# Level_Shifter.net
KiCad netlist of a schematic drawn in EAGLE
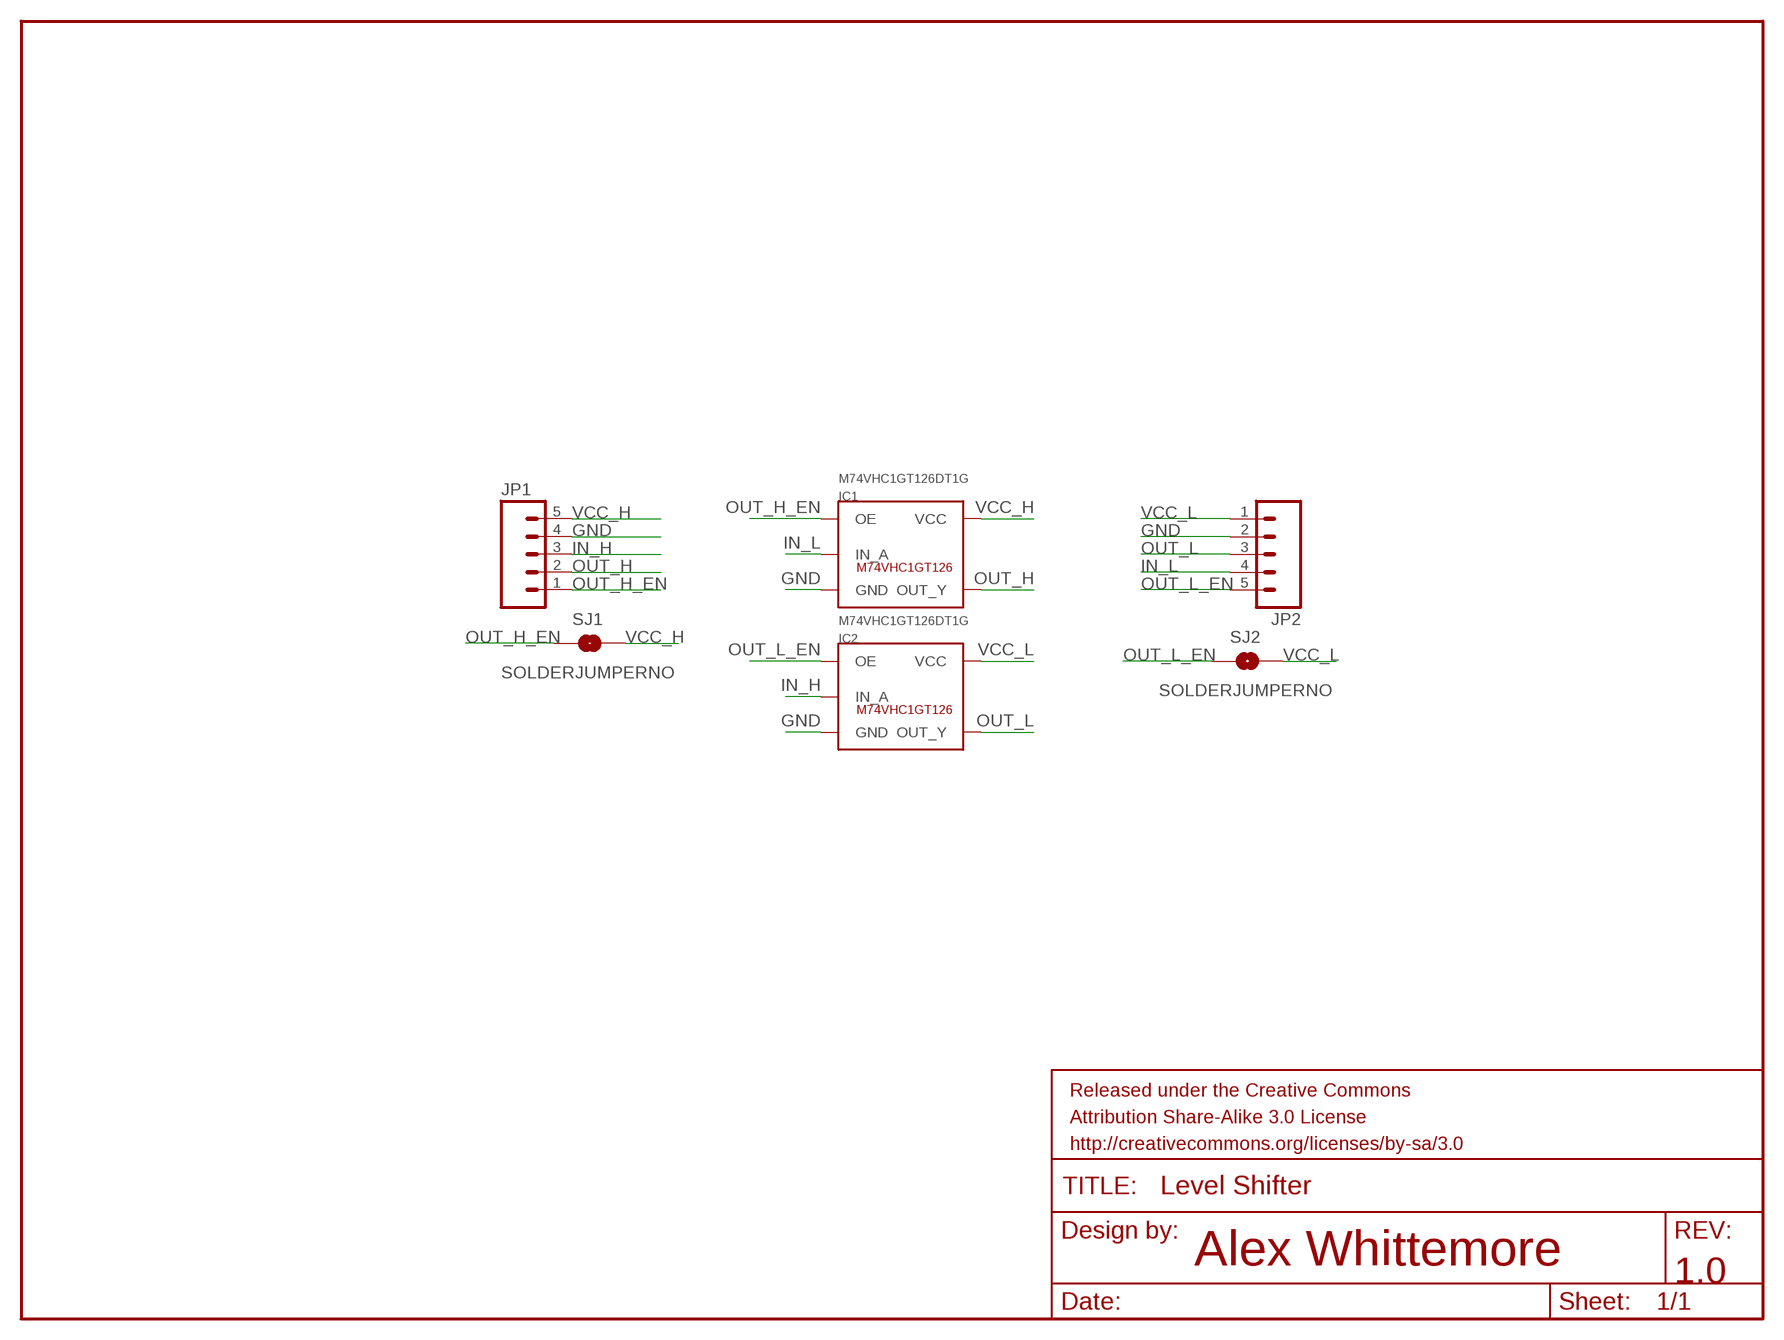
[diagram p0: schematic, sheet 1]

(export (version "E")
  (design (tool "Eeschema 10.0.6"))
  (components
    (comp (ref "IC1")
      (value "M74VHC1GT126DT1G")
      (footprint "eagle-import:SOT23-5L")
      (libsource (lib "eagle-import") (part "M74VHC1GT126DT1G"))
    )
    (comp (ref "IC2")
      (value "M74VHC1GT126DT1G")
      (footprint "eagle-import:SOT23-5L")
      (libsource (lib "eagle-import") (part "M74VHC1GT126DT1G"))
    )
    (comp (ref "JP1")
      (value "M05LOCK")
      (footprint "eagle-import:1X05_LOCK")
      (libsource (lib "eagle-import") (part "M05LOCK"))
    )
    (comp (ref "JP2")
      (value "M05LOCK")
      (footprint "eagle-import:1X05_LOCK")
      (libsource (lib "eagle-import") (part "M05LOCK"))
    )
    (comp (ref "SJ1")
      (value "SOLDERJUMPERNO")
      (footprint "eagle-import:SJ_2S-NO")
      (libsource (lib "eagle-import") (part "SOLDERJUMPERNO"))
    )
    (comp (ref "SJ2")
      (value "SOLDERJUMPERNO")
      (footprint "eagle-import:SJ_2S-NO")
      (libsource (lib "eagle-import") (part "SOLDERJUMPERNO"))
    )
  )
  (nets
    (net (code "1") (name "/GND") (class "Default")
      (node (ref "IC1") (pin "3") (pinfunction "GND_3") (pintype "bidirectional"))
      (node (ref "IC2") (pin "3") (pinfunction "GND_3") (pintype "bidirectional"))
      (node (ref "JP1") (pin "4") (pinfunction "4_4") (pintype "passive"))
      (node (ref "JP2") (pin "2") (pinfunction "2_2") (pintype "passive"))
    )
    (net (code "2") (name "/IN_H") (class "Default")
      (node (ref "IC2") (pin "2") (pinfunction "IN_A_2") (pintype "bidirectional"))
      (node (ref "JP1") (pin "3") (pinfunction "3_3") (pintype "passive"))
    )
    (net (code "3") (name "/IN_L") (class "Default")
      (node (ref "IC1") (pin "2") (pinfunction "IN_A_2") (pintype "bidirectional"))
      (node (ref "JP2") (pin "4") (pinfunction "4_4") (pintype "passive"))
    )
    (net (code "4") (name "/OUT_H") (class "Default")
      (node (ref "IC1") (pin "4") (pinfunction "OUT_Y_4") (pintype "bidirectional"))
      (node (ref "JP1") (pin "2") (pinfunction "2_2") (pintype "passive"))
    )
    (net (code "5") (name "/OUT_H_EN") (class "Default")
      (node (ref "IC1") (pin "1") (pinfunction "OE_1") (pintype "bidirectional"))
      (node (ref "JP1") (pin "1") (pinfunction "1_1") (pintype "passive"))
      (node (ref "SJ1") (pin "1") (pinfunction "1_1") (pintype "passive"))
    )
    (net (code "6") (name "/OUT_L") (class "Default")
      (node (ref "IC2") (pin "4") (pinfunction "OUT_Y_4") (pintype "bidirectional"))
      (node (ref "JP2") (pin "3") (pinfunction "3_3") (pintype "passive"))
    )
    (net (code "7") (name "/OUT_L_EN") (class "Default")
      (node (ref "IC2") (pin "1") (pinfunction "OE_1") (pintype "bidirectional"))
      (node (ref "JP2") (pin "5") (pinfunction "5_5") (pintype "passive"))
      (node (ref "SJ2") (pin "1") (pinfunction "1_1") (pintype "passive"))
    )
    (net (code "8") (name "/VCC_H") (class "Default")
      (node (ref "IC1") (pin "5") (pinfunction "VCC_5") (pintype "bidirectional"))
      (node (ref "JP1") (pin "5") (pinfunction "5_5") (pintype "passive"))
      (node (ref "SJ1") (pin "2") (pinfunction "2_2") (pintype "passive"))
    )
    (net (code "9") (name "/VCC_L") (class "Default")
      (node (ref "IC2") (pin "5") (pinfunction "VCC_5") (pintype "bidirectional"))
      (node (ref "JP2") (pin "1") (pinfunction "1_1") (pintype "passive"))
      (node (ref "SJ2") (pin "2") (pinfunction "2_2") (pintype "passive"))
    )
  )
)
